# TimeSeedsControls.net
KiCad netlist of a schematic drawn in EAGLE
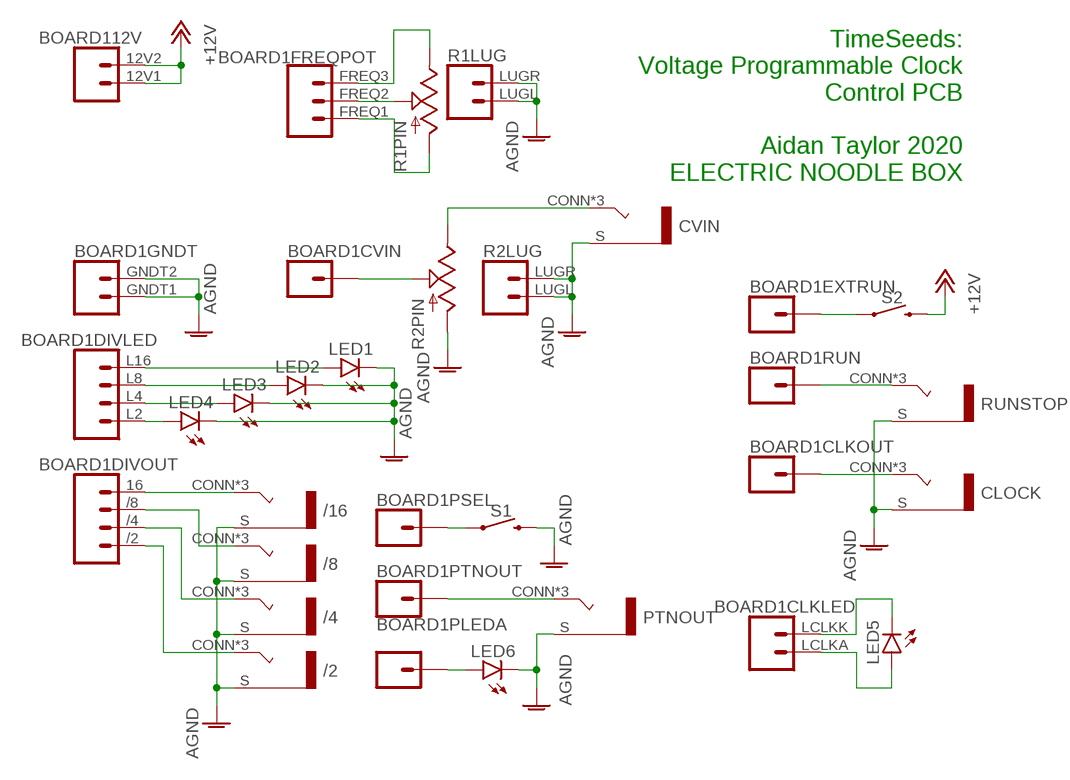
[diagram p0: schematic, sheet 1]

(export (version "E")
  (design (tool "Eeschema 10.0.6"))
  (components
    (comp (ref "/2")
      (value "COMBI-JACKCINCHNANA")
      (footprint "eagle-import:NEWCOMBOJACK_PANEL")
      (libsource (lib "eagle-import") (part "COMBI-JACKCINCHNANA"))
    )
    (comp (ref "/4")
      (value "COMBI-JACKCINCHNANA")
      (footprint "eagle-import:NEWCOMBOJACK_PANEL")
      (libsource (lib "eagle-import") (part "COMBI-JACKCINCHNANA"))
    )
    (comp (ref "/8")
      (value "COMBI-JACKCINCHNANA")
      (footprint "eagle-import:NEWCOMBOJACK_PANEL")
      (libsource (lib "eagle-import") (part "COMBI-JACKCINCHNANA"))
    )
    (comp (ref "/16")
      (value "COMBI-JACKCINCHNANA")
      (footprint "eagle-import:NEWCOMBOJACK_PANEL")
      (libsource (lib "eagle-import") (part "COMBI-JACKCINCHNANA"))
    )
    (comp (ref "BOARD1")
      (value "TS-VPC_LINK")
      (footprint "eagle-import:TS-VPC")
      (libsource (lib "eagle-import") (part "TS-VPC_LINK"))
    )
    (comp (ref "CLOCK")
      (value "COMBI-JACKCINCHNANA")
      (footprint "eagle-import:NEWCOMBOJACK_PANEL")
      (libsource (lib "eagle-import") (part "COMBI-JACKCINCHNANA"))
    )
    (comp (ref "CVIN")
      (value "COMBI-JACKCINCHNANA")
      (footprint "eagle-import:NEWCOMBOJACK_PANEL")
      (libsource (lib "eagle-import") (part "COMBI-JACKCINCHNANA"))
    )
    (comp (ref "LED1")
      (value "LED3MM")
      (footprint "eagle-import:LED3MM")
      (libsource (lib "eagle-import") (part "LED3MM"))
    )
    (comp (ref "LED2")
      (value "LED3MM")
      (footprint "eagle-import:LED3MM")
      (libsource (lib "eagle-import") (part "LED3MM"))
    )
    (comp (ref "LED3")
      (value "LED3MM")
      (footprint "eagle-import:LED3MM")
      (libsource (lib "eagle-import") (part "LED3MM"))
    )
    (comp (ref "LED4")
      (value "LED3MM")
      (footprint "eagle-import:LED3MM")
      (libsource (lib "eagle-import") (part "LED3MM"))
    )
    (comp (ref "LED5")
      (value "LED3MM")
      (footprint "eagle-import:LED3MM")
      (libsource (lib "eagle-import") (part "LED3MM"))
    )
    (comp (ref "LED6")
      (value "LED3MM")
      (footprint "eagle-import:LED3MM")
      (libsource (lib "eagle-import") (part "LED3MM"))
    )
    (comp (ref "PTNOUT")
      (value "COMBI-JACKCINCHNANA")
      (footprint "eagle-import:NEWCOMBOJACK_PANEL")
      (libsource (lib "eagle-import") (part "COMBI-JACKCINCHNANA"))
    )
    (comp (ref "R1")
      (value "POTENTIOMETER")
      (footprint "eagle-import:ALPHA_RV09_9MMPOT")
      (libsource (lib "eagle-import") (part "POTENTIOMETER"))
    )
    (comp (ref "R2")
      (value "POTENTIOMETER")
      (footprint "eagle-import:ALPHA_RV09_9MMPOT")
      (libsource (lib "eagle-import") (part "POTENTIOMETER"))
    )
    (comp (ref "RUNSTOP")
      (value "COMBI-JACKCINCHNANA")
      (footprint "eagle-import:NEWCOMBOJACK_PANEL")
      (libsource (lib "eagle-import") (part "COMBI-JACKCINCHNANA"))
    )
    (comp (ref "S1")
      (value "MCDTS-2_PUSHBUTTON")
      (footprint "eagle-import:MCDTS-2_PUSHBUTTON")
      (libsource (lib "eagle-import") (part "MCDTS-2_PUSHBUTTON"))
    )
    (comp (ref "S2")
      (value "MCDTS-2_PUSHBUTTON")
      (footprint "eagle-import:MCDTS-2_PUSHBUTTON")
      (libsource (lib "eagle-import") (part "MCDTS-2_PUSHBUTTON"))
    )
  )
  (nets
    (net (code "1") (name "+12V") (class "Default")
      (node (ref "BOARD1") (pin "12V1") (pinfunction "1_12V1") (pintype "passive"))
      (node (ref "BOARD1") (pin "12V2") (pinfunction "2_12V2") (pintype "passive"))
      (node (ref "S2") (pin "P$3") (pinfunction "2_P$3") (pintype "passive"))
      (node (ref "S2") (pin "P$4") (pinfunction "2_P$4") (pintype "passive"))
    )
    (net (code "2") (name "AGND") (class "Default")
      (node (ref "/16") (pin "S") (pinfunction "S_S") (pintype "passive"))
      (node (ref "/2") (pin "S") (pinfunction "S_S") (pintype "passive"))
      (node (ref "/4") (pin "S") (pinfunction "S_S") (pintype "passive"))
      (node (ref "/8") (pin "S") (pinfunction "S_S") (pintype "passive"))
      (node (ref "BOARD1") (pin "GNDT1") (pinfunction "1_GNDT1") (pintype "passive"))
      (node (ref "BOARD1") (pin "GNDT2") (pinfunction "2_GNDT2") (pintype "passive"))
      (node (ref "CLOCK") (pin "S") (pinfunction "S_S") (pintype "passive"))
      (node (ref "CVIN") (pin "S") (pinfunction "S_S") (pintype "passive"))
      (node (ref "LED1") (pin "K") (pinfunction "C_K") (pintype "passive"))
      (node (ref "LED2") (pin "K") (pinfunction "C_K") (pintype "passive"))
      (node (ref "LED3") (pin "K") (pinfunction "C_K") (pintype "passive"))
      (node (ref "LED4") (pin "K") (pinfunction "C_K") (pintype "passive"))
      (node (ref "LED6") (pin "K") (pinfunction "C_K") (pintype "passive"))
      (node (ref "PTNOUT") (pin "S") (pinfunction "S_S") (pintype "passive"))
      (node (ref "R1") (pin "LUGL") (pinfunction "1_LUGL") (pintype "passive"))
      (node (ref "R1") (pin "LUGR") (pinfunction "2_LUGR") (pintype "passive"))
      (node (ref "R2") (pin "C1") (pinfunction "A_C1") (pintype "passive"))
      (node (ref "R2") (pin "LUGL") (pinfunction "1_LUGL") (pintype "passive"))
      (node (ref "R2") (pin "LUGR") (pinfunction "2_LUGR") (pintype "passive"))
      (node (ref "RUNSTOP") (pin "S") (pinfunction "S_S") (pintype "passive"))
      (node (ref "S1") (pin "P$3") (pinfunction "2_P$3") (pintype "passive"))
      (node (ref "S1") (pin "P$4") (pinfunction "2_P$4") (pintype "passive"))
    )
    (net (code "3") (name "Net-(BOARD1B-1)") (class "Default")
      (node (ref "BOARD1") (pin "LCLKA") (pinfunction "1_LCLKA") (pintype "passive"))
      (node (ref "LED5") (pin "A") (pinfunction "A_A") (pintype "passive"))
    )
    (net (code "4") (name "Net-(BOARD1B-2)") (class "Default")
      (node (ref "BOARD1") (pin "LCLKK") (pinfunction "2_LCLKK") (pintype "passive"))
      (node (ref "LED5") (pin "K") (pinfunction "C_K") (pintype "passive"))
    )
    (net (code "5") (name "Net-(BOARD1C-1)") (class "Default")
      (node (ref "BOARD1") (pin "CLK") (pinfunction "1_CLK") (pintype "passive"))
      (node (ref "CLOCK") (pin "CONN") (pinfunction "T_CONN") (pintype "passive"))
      (node (ref "CLOCK") (pin "T1") (pinfunction "T_T1") (pintype "passive"))
      (node (ref "CLOCK") (pin "T2") (pinfunction "T_T2") (pintype "passive"))
    )
    (net (code "6") (name "Net-(BOARD1D-1)") (class "Default")
      (node (ref "BOARD1") (pin "CVIN") (pinfunction "1_CVIN") (pintype "passive"))
      (node (ref "R2") (pin "C2") (pinfunction "W_C2") (pintype "passive"))
    )
    (net (code "7") (name "Net-(BOARD1E-1)") (class "Default")
      (node (ref "BOARD1") (pin "L2") (pinfunction "1_L2") (pintype "passive"))
      (node (ref "LED4") (pin "A") (pinfunction "A_A") (pintype "passive"))
    )
    (net (code "8") (name "Net-(BOARD1E-2)") (class "Default")
      (node (ref "BOARD1") (pin "L4") (pinfunction "2_L4") (pintype "passive"))
      (node (ref "LED3") (pin "A") (pinfunction "A_A") (pintype "passive"))
    )
    (net (code "9") (name "Net-(BOARD1E-3)") (class "Default")
      (node (ref "BOARD1") (pin "L8") (pinfunction "3_L8") (pintype "passive"))
      (node (ref "LED2") (pin "A") (pinfunction "A_A") (pintype "passive"))
    )
    (net (code "10") (name "Net-(BOARD1E-4)") (class "Default")
      (node (ref "BOARD1") (pin "L16") (pinfunction "4_L16") (pintype "passive"))
      (node (ref "LED1") (pin "A") (pinfunction "A_A") (pintype "passive"))
    )
    (net (code "11") (name "Net-(BOARD1F-1)") (class "Default")
      (node (ref "/2") (pin "CONN") (pinfunction "T_CONN") (pintype "passive"))
      (node (ref "/2") (pin "T1") (pinfunction "T_T1") (pintype "passive"))
      (node (ref "/2") (pin "T2") (pinfunction "T_T2") (pintype "passive"))
      (node (ref "BOARD1") (pin "/2") (pinfunction "1_/2") (pintype "passive"))
    )
    (net (code "12") (name "Net-(BOARD1F-2)") (class "Default")
      (node (ref "/4") (pin "CONN") (pinfunction "T_CONN") (pintype "passive"))
      (node (ref "/4") (pin "T1") (pinfunction "T_T1") (pintype "passive"))
      (node (ref "/4") (pin "T2") (pinfunction "T_T2") (pintype "passive"))
      (node (ref "BOARD1") (pin "/4") (pinfunction "2_/4") (pintype "passive"))
    )
    (net (code "13") (name "Net-(BOARD1F-3)") (class "Default")
      (node (ref "/8") (pin "CONN") (pinfunction "T_CONN") (pintype "passive"))
      (node (ref "/8") (pin "T1") (pinfunction "T_T1") (pintype "passive"))
      (node (ref "/8") (pin "T2") (pinfunction "T_T2") (pintype "passive"))
      (node (ref "BOARD1") (pin "/8") (pinfunction "3_/8") (pintype "passive"))
    )
    (net (code "14") (name "Net-(BOARD1F-4)") (class "Default")
      (node (ref "/16") (pin "CONN") (pinfunction "T_CONN") (pintype "passive"))
      (node (ref "/16") (pin "T1") (pinfunction "T_T1") (pintype "passive"))
      (node (ref "/16") (pin "T2") (pinfunction "T_T2") (pintype "passive"))
      (node (ref "BOARD1") (pin "16") (pinfunction "4_16") (pintype "passive"))
    )
    (net (code "15") (name "Net-(BOARD1G-1)") (class "Default")
      (node (ref "BOARD1") (pin "EXTRUN") (pinfunction "1_EXTRUN") (pintype "passive"))
      (node (ref "S2") (pin "P$1") (pinfunction "1_P$1") (pintype "passive"))
      (node (ref "S2") (pin "P$2") (pinfunction "1_P$2") (pintype "passive"))
    )
    (net (code "16") (name "Net-(BOARD1H-1)") (class "Default")
      (node (ref "BOARD1") (pin "FREQ1") (pinfunction "1_FREQ1") (pintype "passive"))
      (node (ref "R1") (pin "C1") (pinfunction "A_C1") (pintype "passive"))
    )
    (net (code "17") (name "Net-(BOARD1H-2)") (class "Default")
      (node (ref "BOARD1") (pin "FREQ2") (pinfunction "2_FREQ2") (pintype "passive"))
      (node (ref "R1") (pin "C2") (pinfunction "W_C2") (pintype "passive"))
    )
    (net (code "18") (name "Net-(BOARD1H-3)") (class "Default")
      (node (ref "BOARD1") (pin "FREQ3") (pinfunction "3_FREQ3") (pintype "passive"))
      (node (ref "R1") (pin "C3") (pinfunction "B_C3") (pintype "passive"))
    )
    (net (code "19") (name "Net-(BOARD1J-1)") (class "Default")
      (node (ref "BOARD1") (pin "PLEDA") (pinfunction "1_PLEDA") (pintype "passive"))
      (node (ref "LED6") (pin "A") (pinfunction "A_A") (pintype "passive"))
    )
    (net (code "20") (name "Net-(BOARD1K-1)") (class "Default")
      (node (ref "BOARD1") (pin "PSEL") (pinfunction "1_PSEL") (pintype "passive"))
      (node (ref "S1") (pin "P$1") (pinfunction "1_P$1") (pintype "passive"))
      (node (ref "S1") (pin "P$2") (pinfunction "1_P$2") (pintype "passive"))
    )
    (net (code "21") (name "Net-(BOARD1L-1)") (class "Default")
      (node (ref "BOARD1") (pin "PTRNOUT") (pinfunction "1_PTRNOUT") (pintype "passive"))
      (node (ref "PTNOUT") (pin "CONN") (pinfunction "T_CONN") (pintype "passive"))
      (node (ref "PTNOUT") (pin "T1") (pinfunction "T_T1") (pintype "passive"))
      (node (ref "PTNOUT") (pin "T2") (pinfunction "T_T2") (pintype "passive"))
    )
    (net (code "22") (name "Net-(BOARD1M-1)") (class "Default")
      (node (ref "BOARD1") (pin "RUN") (pinfunction "1_RUN") (pintype "passive"))
      (node (ref "RUNSTOP") (pin "CONN") (pinfunction "T_CONN") (pintype "passive"))
      (node (ref "RUNSTOP") (pin "T1") (pinfunction "T_T1") (pintype "passive"))
      (node (ref "RUNSTOP") (pin "T2") (pinfunction "T_T2") (pintype "passive"))
    )
    (net (code "23") (name "Net-(R2B-B)") (class "Default")
      (node (ref "CVIN") (pin "CONN") (pinfunction "T_CONN") (pintype "passive"))
      (node (ref "CVIN") (pin "T1") (pinfunction "T_T1") (pintype "passive"))
      (node (ref "CVIN") (pin "T2") (pinfunction "T_T2") (pintype "passive"))
      (node (ref "R2") (pin "C3") (pinfunction "B_C3") (pintype "passive"))
    )
  )
)
